# pure_energy.net
KiCad netlist of a schematic drawn in EAGLE
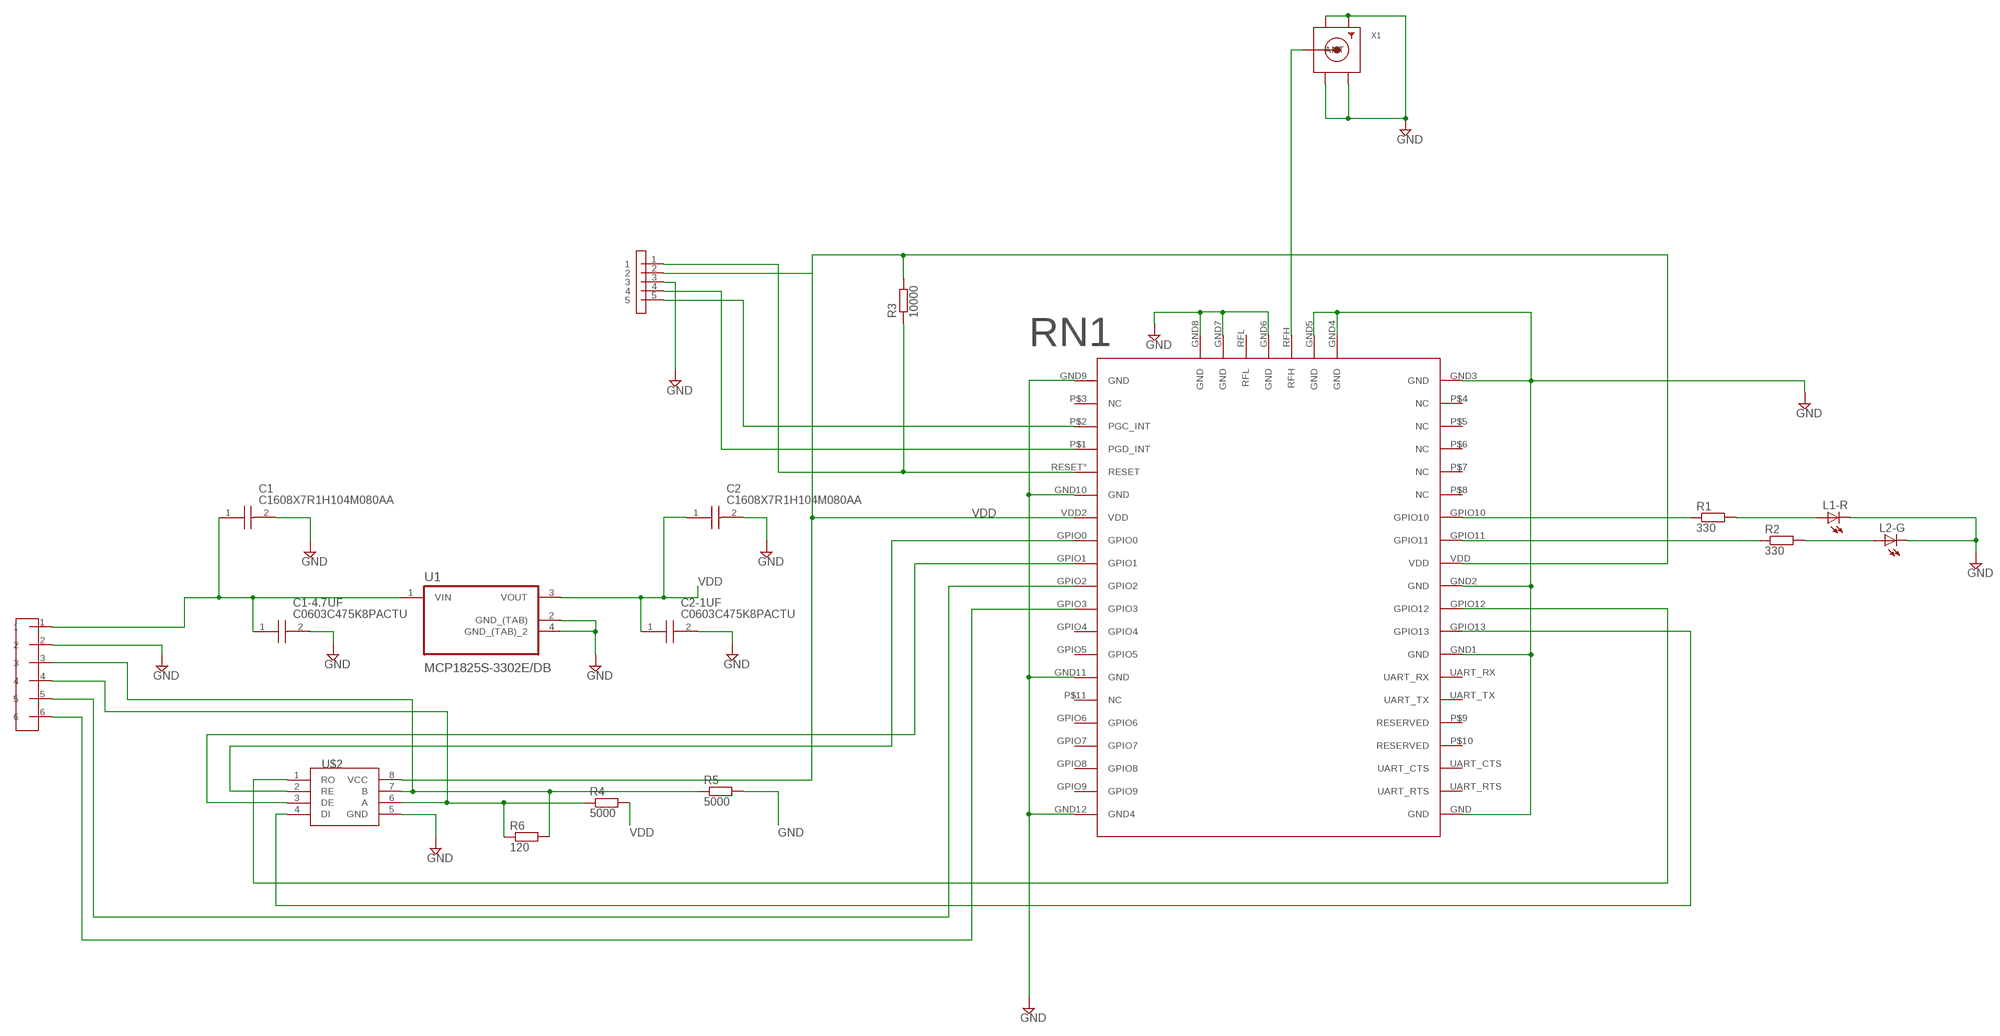
[diagram p0: schematic, sheet 1]

(export (version "E")
  (design (tool "Eeschema 10.0.6"))
  (components
    (comp (ref "C1")
      (value "C1608X7R1H104M080AA")
      (footprint "eagle-import:CAPC1608X80N")
      (fields (field (name "MOUSER_PART_NUMBER") "810-C1608X7R1H104M"))
      (libsource (lib "eagle-import") (part "C1608X7R1H104M080AA"))
    )
    (comp (ref "C1-4.7UF")
      (value "C0603C475K8PACTU")
      (footprint "eagle-import:CAPC1608X85N")
      (fields (field (name "MOUSER_PART_NUMBER") "80-C0603C475K8P"))
      (libsource (lib "eagle-import") (part "C0603C475K8PACTU"))
    )
    (comp (ref "C2")
      (value "C1608X7R1H104M080AA")
      (footprint "eagle-import:CAPC1608X80N")
      (fields (field (name "MOUSER_PART_NUMBER") "810-C1608X7R1H104M"))
      (libsource (lib "eagle-import") (part "C1608X7R1H104M080AA"))
    )
    (comp (ref "C2-1UF")
      (value "C0603C475K8PACTU")
      (footprint "eagle-import:CAPC1608X85N")
      (fields (field (name "MOUSER_PART_NUMBER") "80-C0603C475K8P"))
      (libsource (lib "eagle-import") (part "C0603C475K8PACTU"))
    )
    (comp (ref "L1-R")
      (value "LEDCHIP-LED0603")
      (footprint "eagle-import:CHIP-LED0603")
      (libsource (lib "eagle-import") (part "LEDCHIP-LED0603"))
    )
    (comp (ref "L2-G")
      (value "LEDCHIP-LED0603")
      (footprint "eagle-import:CHIP-LED0603")
      (libsource (lib "eagle-import") (part "LEDCHIP-LED0603"))
    )
    (comp (ref "R1")
      (value "330")
      (footprint "eagle-import:R0603")
      (libsource (lib "eagle-import") (part "R-EU_R0603"))
    )
    (comp (ref "R2")
      (value "330")
      (footprint "eagle-import:R0603")
      (libsource (lib "eagle-import") (part "R-EU_R0603"))
    )
    (comp (ref "R3")
      (value "10000")
      (footprint "eagle-import:R0603")
      (libsource (lib "eagle-import") (part "R-EU_R0603"))
    )
    (comp (ref "R4")
      (value "5000")
      (footprint "eagle-import:R0805")
      (libsource (lib "eagle-import") (part "R-EU_R0805"))
    )
    (comp (ref "R5")
      (value "5000")
      (footprint "eagle-import:R0805")
      (libsource (lib "eagle-import") (part "R-EU_R0805"))
    )
    (comp (ref "R6")
      (value "120")
      (footprint "eagle-import:R0805")
      (libsource (lib "eagle-import") (part "R-EU_R0805"))
    )
    (comp (ref "RN1")
      (value "NEW_RN2483")
      (footprint "eagle-import:NEW_RN2483")
      (libsource (lib "eagle-import") (part "NEW_RN2483"))
    )
    (comp (ref "U$1")
      (value "CONNECTOR62")
      (footprint "eagle-import:CONNECTOR6")
      (libsource (lib "eagle-import") (part "CONNECTOR62"))
    )
    (comp (ref "U$2")
      (value "AMD3485E")
      (footprint "eagle-import:AMD3485E")
      (libsource (lib "eagle-import") (part "AMD3485E"))
    )
    (comp (ref "U$3")
      (value "ICSP52")
      (footprint "eagle-import:ICSP")
      (libsource (lib "eagle-import") (part "ICSP52"))
    )
    (comp (ref "U1")
      (value "MCP1825S-3302E/DB")
      (footprint "eagle-import:SOT230P700X180-4N")
      (fields (field (name "MF") "Microchip"))
      (libsource (lib "eagle-import") (part "MCP1825S-3302E/DB"))
    )
    (comp (ref "X1")
      (value "SMACONNECTOR_EDGE")
      (footprint "eagle-import:SMA_EDGELAUNCH")
      (libsource (lib "eagle-import") (part "SMACONNECTOR_EDGE"))
    )
  )
  (nets
    (net (code "1") (name "/VDD") (class "Default")
      (node (ref "C2") (pin "1") (pinfunction "1_1") (pintype "bidirectional"))
      (node (ref "C2-1UF") (pin "1") (pinfunction "C1_1") (pintype "bidirectional"))
      (node (ref "R3") (pin "2") (pinfunction "2_2") (pintype "passive"))
      (node (ref "R4") (pin "2") (pinfunction "2_2") (pintype "passive"))
      (node (ref "RN1") (pin "VDD") (pinfunction "VDD_VDD") (pintype "bidirectional"))
      (node (ref "RN1") (pin "VDD2") (pinfunction "VDD_VDD2") (pintype "bidirectional"))
      (node (ref "U$2") (pin "8") (pinfunction "VCC_8") (pintype "bidirectional"))
      (node (ref "U$3") (pin "2") (pinfunction "2_2") (pintype "bidirectional"))
      (node (ref "U1") (pin "3") (pinfunction "VOUT_3") (pintype "output"))
    )
    (net (code "2") (name "GND") (class "Default")
      (node (ref "C1") (pin "2") (pinfunction "2_2") (pintype "bidirectional"))
      (node (ref "C1-4.7UF") (pin "2") (pinfunction "C2_2") (pintype "bidirectional"))
      (node (ref "C2") (pin "2") (pinfunction "2_2") (pintype "bidirectional"))
      (node (ref "C2-1UF") (pin "2") (pinfunction "C2_2") (pintype "bidirectional"))
      (node (ref "L1-R") (pin "C") (pinfunction "C_C") (pintype "passive"))
      (node (ref "L2-G") (pin "C") (pinfunction "C_C") (pintype "passive"))
      (node (ref "R5") (pin "2") (pinfunction "2_2") (pintype "passive"))
      (node (ref "RN1") (pin "GND") (pinfunction "GND_GND") (pintype "bidirectional"))
      (node (ref "RN1") (pin "GND1") (pinfunction "GND_GND1") (pintype "bidirectional"))
      (node (ref "RN1") (pin "GND10") (pinfunction "GND_GND10") (pintype "bidirectional"))
      (node (ref "RN1") (pin "GND11") (pinfunction "GND_GND11") (pintype "bidirectional"))
      (node (ref "RN1") (pin "GND12") (pinfunction "GND4_GND12") (pintype "bidirectional"))
      (node (ref "RN1") (pin "GND2") (pinfunction "GND_GND2") (pintype "bidirectional"))
      (node (ref "RN1") (pin "GND3") (pinfunction "GND_GND3") (pintype "bidirectional"))
      (node (ref "RN1") (pin "GND4") (pinfunction "GND_GND4") (pintype "bidirectional"))
      (node (ref "RN1") (pin "GND5") (pinfunction "GND_GND5") (pintype "bidirectional"))
      (node (ref "RN1") (pin "GND6") (pinfunction "GND_GND6") (pintype "bidirectional"))
      (node (ref "RN1") (pin "GND7") (pinfunction "GND_GND7") (pintype "bidirectional"))
      (node (ref "RN1") (pin "GND8") (pinfunction "GND_GND8") (pintype "bidirectional"))
      (node (ref "RN1") (pin "GND9") (pinfunction "GND_GND9") (pintype "bidirectional"))
      (node (ref "U$1") (pin "2") (pinfunction "2_2") (pintype "bidirectional"))
      (node (ref "U$2") (pin "5") (pinfunction "GND_5") (pintype "bidirectional"))
      (node (ref "U$3") (pin "3") (pinfunction "3_3") (pintype "bidirectional"))
      (node (ref "U1") (pin "2") (pinfunction "GND_(TAB)_2") (pintype "power_in"))
      (node (ref "U1") (pin "4") (pinfunction "GND_(TAB)_2_4") (pintype "power_in"))
      (node (ref "X1") (pin "GND@1") (pinfunction "GND4_GND@1") (pintype "power_in"))
      (node (ref "X1") (pin "GND@2") (pinfunction "GND3_GND@2") (pintype "power_in"))
      (node (ref "X1") (pin "GND@3") (pinfunction "GND2_GND@3") (pintype "power_in"))
      (node (ref "X1") (pin "GND@4") (pinfunction "GND1_GND@4") (pintype "power_in"))
    )
    (net (code "3") (name "Net-(C1-4.7UF-C1)") (class "Default")
      (node (ref "C1") (pin "1") (pinfunction "1_1") (pintype "bidirectional"))
      (node (ref "C1-4.7UF") (pin "1") (pinfunction "C1_1") (pintype "bidirectional"))
      (node (ref "U$1") (pin "1") (pinfunction "1_1") (pintype "bidirectional"))
      (node (ref "U1") (pin "1") (pinfunction "VIN_1") (pintype "input"))
    )
    (net (code "4") (name "Net-(L1-R-PadA)") (class "Default")
      (node (ref "L1-R") (pin "A") (pinfunction "A_A") (pintype "passive"))
      (node (ref "R1") (pin "2") (pinfunction "2_2") (pintype "passive"))
    )
    (net (code "5") (name "Net-(L2-G-PadA)") (class "Default")
      (node (ref "L2-G") (pin "A") (pinfunction "A_A") (pintype "passive"))
      (node (ref "R2") (pin "2") (pinfunction "2_2") (pintype "passive"))
    )
    (net (code "6") (name "Net-(R1-Pad1)") (class "Default")
      (node (ref "R1") (pin "1") (pinfunction "1_1") (pintype "passive"))
      (node (ref "RN1") (pin "GPIO10") (pinfunction "GPIO10_GPIO10") (pintype "bidirectional"))
    )
    (net (code "7") (name "Net-(R2-Pad1)") (class "Default")
      (node (ref "R2") (pin "1") (pinfunction "1_1") (pintype "passive"))
      (node (ref "RN1") (pin "GPIO11") (pinfunction "GPIO11_GPIO11") (pintype "bidirectional"))
    )
    (net (code "8") (name "Net-(RN1-PGC_INT)") (class "Default")
      (node (ref "RN1") (pin "P$2") (pinfunction "PGC_INT_P$2") (pintype "bidirectional"))
      (node (ref "U$3") (pin "5") (pinfunction "5_5") (pintype "bidirectional"))
    )
    (net (code "9") (name "Net-(RN1-PGD_INT)") (class "Default")
      (node (ref "RN1") (pin "P$1") (pinfunction "PGD_INT_P$1") (pintype "bidirectional"))
      (node (ref "U$3") (pin "4") (pinfunction "4_4") (pintype "bidirectional"))
    )
    (net (code "10") (name "Net-(RN1-PadGPIO2)") (class "Default")
      (node (ref "RN1") (pin "GPIO2") (pinfunction "GPIO2_GPIO2") (pintype "bidirectional"))
      (node (ref "U$1") (pin "5") (pinfunction "5_5") (pintype "bidirectional"))
    )
    (net (code "11") (name "Net-(RN1-PadGPIO3)") (class "Default")
      (node (ref "RN1") (pin "GPIO3") (pinfunction "GPIO3_GPIO3") (pintype "bidirectional"))
      (node (ref "U$1") (pin "6") (pinfunction "6_6") (pintype "bidirectional"))
    )
    (net (code "12") (name "Net-(RN1-RESET)") (class "Default")
      (node (ref "R3") (pin "1") (pinfunction "1_1") (pintype "passive"))
      (node (ref "RN1") (pin "RESET°") (pinfunction "RESET_RESET°") (pintype "bidirectional"))
      (node (ref "U$3") (pin "1") (pinfunction "1_1") (pintype "bidirectional"))
    )
    (net (code "13") (name "Net-(U$2-A)") (class "Default")
      (node (ref "R4") (pin "1") (pinfunction "1_1") (pintype "passive"))
      (node (ref "R6") (pin "1") (pinfunction "1_1") (pintype "passive"))
      (node (ref "U$1") (pin "4") (pinfunction "4_4") (pintype "bidirectional"))
      (node (ref "U$2") (pin "6") (pinfunction "A_6") (pintype "bidirectional"))
    )
    (net (code "14") (name "Net-(U$2-B)") (class "Default")
      (node (ref "R5") (pin "1") (pinfunction "1_1") (pintype "passive"))
      (node (ref "R6") (pin "2") (pinfunction "2_2") (pintype "passive"))
      (node (ref "U$1") (pin "3") (pinfunction "3_3") (pintype "bidirectional"))
      (node (ref "U$2") (pin "7") (pinfunction "B_7") (pintype "bidirectional"))
    )
    (net (code "15") (name "Net-(U$2-DE)") (class "Default")
      (node (ref "RN1") (pin "GPIO1") (pinfunction "GPIO1_GPIO1") (pintype "bidirectional"))
      (node (ref "U$2") (pin "3") (pinfunction "DE_3") (pintype "bidirectional"))
    )
    (net (code "16") (name "Net-(U$2-DI)") (class "Default")
      (node (ref "RN1") (pin "GPIO13") (pinfunction "GPIO13_GPIO13") (pintype "bidirectional"))
      (node (ref "U$2") (pin "4") (pinfunction "DI_4") (pintype "bidirectional"))
    )
    (net (code "17") (name "Net-(U$2-RE)") (class "Default")
      (node (ref "RN1") (pin "GPIO0") (pinfunction "GPIO0_GPIO0") (pintype "bidirectional"))
      (node (ref "U$2") (pin "2") (pinfunction "RE_2") (pintype "bidirectional"))
    )
    (net (code "18") (name "Net-(U$2-RO)") (class "Default")
      (node (ref "RN1") (pin "GPIO12") (pinfunction "GPIO12_GPIO12") (pintype "bidirectional"))
      (node (ref "U$2") (pin "1") (pinfunction "RO_1") (pintype "bidirectional"))
    )
    (net (code "19") (name "Net-(X1-ANT)") (class "Default")
      (node (ref "RN1") (pin "RFH") (pinfunction "RFH_RFH") (pintype "bidirectional"))
      (node (ref "X1") (pin "P") (pinfunction "ANT_P") (pintype "bidirectional"))
    )
    (net (code "20") (name "unconnected-(RN1-NC-PadP$3)") (class "Default")
      (node (ref "RN1") (pin "P$3") (pinfunction "NC_P$3") (pintype "bidirectional"))
    )
    (net (code "21") (name "unconnected-(RN1-NC-PadP$4)") (class "Default")
      (node (ref "RN1") (pin "P$4") (pinfunction "NC_P$4") (pintype "bidirectional"))
    )
    (net (code "22") (name "unconnected-(RN1-NC-PadP$5)") (class "Default")
      (node (ref "RN1") (pin "P$5") (pinfunction "NC_P$5") (pintype "bidirectional"))
    )
    (net (code "23") (name "unconnected-(RN1-NC-PadP$6)") (class "Default")
      (node (ref "RN1") (pin "P$6") (pinfunction "NC_P$6") (pintype "bidirectional"))
    )
    (net (code "24") (name "unconnected-(RN1-NC-PadP$7)") (class "Default")
      (node (ref "RN1") (pin "P$7") (pinfunction "NC_P$7") (pintype "bidirectional"))
    )
    (net (code "25") (name "unconnected-(RN1-NC-PadP$8)") (class "Default")
      (node (ref "RN1") (pin "P$8") (pinfunction "NC_P$8") (pintype "bidirectional"))
    )
    (net (code "26") (name "unconnected-(RN1-NC-PadP$11)") (class "Default")
      (node (ref "RN1") (pin "P$11") (pinfunction "NC_P$11") (pintype "bidirectional"))
    )
    (net (code "27") (name "unconnected-(RN1-PadGPIO4)") (class "Default")
      (node (ref "RN1") (pin "GPIO4") (pinfunction "GPIO4_GPIO4") (pintype "bidirectional"))
    )
    (net (code "28") (name "unconnected-(RN1-PadGPIO5)") (class "Default")
      (node (ref "RN1") (pin "GPIO5") (pinfunction "GPIO5_GPIO5") (pintype "bidirectional"))
    )
    (net (code "29") (name "unconnected-(RN1-PadGPIO6)") (class "Default")
      (node (ref "RN1") (pin "GPIO6") (pinfunction "GPIO6_GPIO6") (pintype "bidirectional"))
    )
    (net (code "30") (name "unconnected-(RN1-PadGPIO7)") (class "Default")
      (node (ref "RN1") (pin "GPIO7") (pinfunction "GPIO7_GPIO7") (pintype "bidirectional"))
    )
    (net (code "31") (name "unconnected-(RN1-PadGPIO8)") (class "Default")
      (node (ref "RN1") (pin "GPIO8") (pinfunction "GPIO8_GPIO8") (pintype "bidirectional"))
    )
    (net (code "32") (name "unconnected-(RN1-PadGPIO9)") (class "Default")
      (node (ref "RN1") (pin "GPIO9") (pinfunction "GPIO9_GPIO9") (pintype "bidirectional"))
    )
    (net (code "33") (name "unconnected-(RN1-PadRFL)") (class "Default")
      (node (ref "RN1") (pin "RFL") (pinfunction "RFL_RFL") (pintype "bidirectional"))
    )
    (net (code "34") (name "unconnected-(RN1-PadUART_CTS)") (class "Default")
      (node (ref "RN1") (pin "UART_CTS") (pinfunction "UART_CTS_UART_CTS") (pintype "bidirectional"))
    )
    (net (code "35") (name "unconnected-(RN1-PadUART_RTS)") (class "Default")
      (node (ref "RN1") (pin "UART_RTS") (pinfunction "UART_RTS_UART_RTS") (pintype "bidirectional"))
    )
    (net (code "36") (name "unconnected-(RN1-PadUART_RX)") (class "Default")
      (node (ref "RN1") (pin "UART_RX") (pinfunction "UART_RX_UART_RX") (pintype "bidirectional"))
    )
    (net (code "37") (name "unconnected-(RN1-PadUART_TX)") (class "Default")
      (node (ref "RN1") (pin "UART_TX") (pinfunction "UART_TX_UART_TX") (pintype "bidirectional"))
    )
    (net (code "38") (name "unconnected-(RN1-RESERVED-PadP$9)") (class "Default")
      (node (ref "RN1") (pin "P$9") (pinfunction "RESERVED_P$9") (pintype "bidirectional"))
    )
    (net (code "39") (name "unconnected-(RN1-RESERVED-PadP$10)") (class "Default")
      (node (ref "RN1") (pin "P$10") (pinfunction "RESERVED_P$10") (pintype "bidirectional"))
    )
  )
)
